# IO_combined.net
KiCad netlist of a schematic drawn in Altium Designer
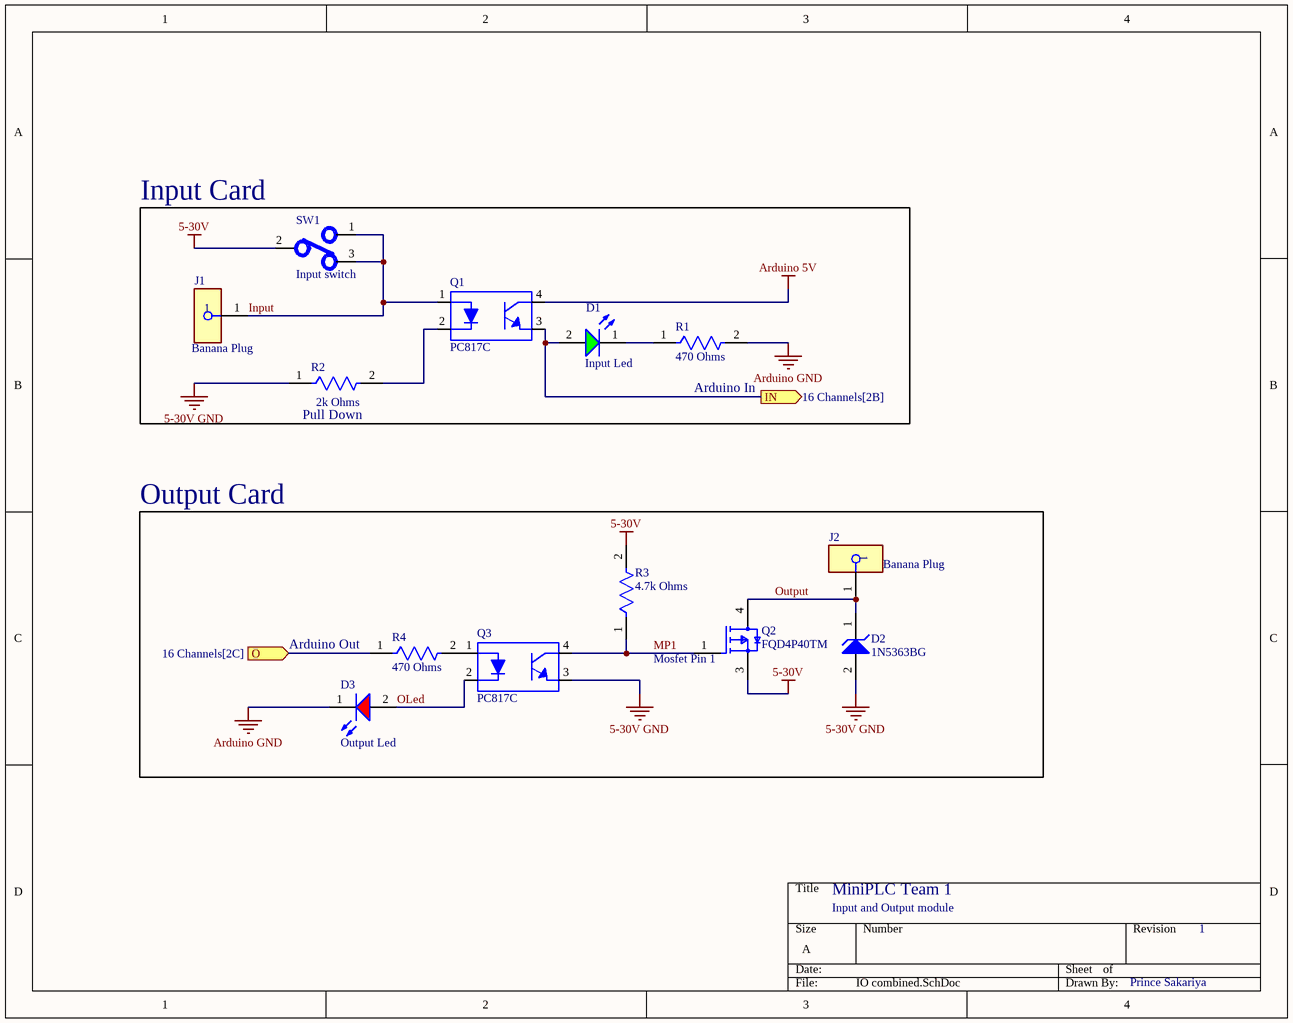
[diagram p0: IO combined.SchDoc]

(export (version "E")
  (design (tool "Eeschema 10.0.6"))
  (components
    (comp (ref "D1")
      (value "Input Led")
      (footprint "WL-TMRW_D5.8H8.6")
      (description "151054GS03000 WL-TMRW THT Mono-color Round Waterclear")
      (libsource (lib "Altium Content Vault") (part "LED_Green_2A-1K"))
    )
    (comp (ref "D2")
      (value "1N5363BG")
      (footprint "ONSC-SURMETIC40-2-017AA-01")
      (description "5 W Zener Voltage Regulator, 2-Pin Surmetic(TM) 40, Pb-Free, Bulk Box")
      (fields (field (name "MANUFACTURER") "On Semiconductor"))
      (libsource (lib "Altium Content Vault") (part "ONSC-K1A2-2"))
    )
    (comp (ref "D3")
      (value "Output Led")
      (footprint "WL-TMRW_D5.8H8.6")
      (description "151054RS03000 WL-TMRW THT Mono-color Round Waterclear")
      (libsource (lib "Altium Content Vault") (part "LED_Red_2A-1K"))
    )
    (comp (ref "J1")
      (value "Banana Plug")
      (footprint "FP-1581-5-MFG")
      (description "CONN BANANA JACK TURRET GREEN")
      (libsource (lib "Altium Content Vault") (part "c5c826e0c4b67fe3b42ef77f2d4decc"))
    )
    (comp (ref "J2")
      (value "Banana Plug")
      (footprint "FP-1581-5-MFG")
      (description "CONN BANANA JACK TURRET GREEN")
      (libsource (lib "") (part "c5c826e0c4b67fe3b42ef77f2d4decc_1"))
    )
    (comp (ref "Q1")
      (value "PC817C")
      (footprint "PC817-DIP")
      (description "Optoisolator Transistor Output 5000Vrms 1 Channel 4-DIP\r\n¦ Designed By @Alixahedi ¦")
      (fields (field (name "MF") "Taiwan Semiconductor"))
      (libsource (lib "SnapEDAsch") (part "PC817C"))
    )
    (comp (ref "Q2")
      (value "FQD4P40TM")
      (footprint "FP-369AS-MFG")
      (description "FQD4P40TM P-channel Power Mosfet, Qfet®, -400 V, -2.7 A, 3.1 Ω, Dpak")
      (libsource (lib "Altium Content Vault") (part "34928d9f04e0aab61442e227171e45b"))
    )
    (comp (ref "Q3")
      (value "PC817C")
      (footprint "PC817-DIP")
      (description "Optoisolator Transistor Output 5000Vrms 1 Channel 4-DIP\r\n¦ Designed By @Alixahedi ¦")
      (fields (field (name "MF") "Taiwan Semiconductor"))
      (libsource (lib "SnapEDAsch") (part "PC817C"))
    )
    (comp (ref "R1")
      (value "470 Ohms")
      (footprint "FP-HVR37-MFG")
      (fields (field (name "TOLERANCE") "1%"))
      (libsource (lib "Altium Content Vault") (part "1029c3af85768c4190bb7ad29bc67b5"))
    )
    (comp (ref "R2")
      (value "2k Ohms")
      (footprint "FP-HVR37-MFG")
      (fields (field (name "TOLERANCE") "1%"))
      (libsource (lib "Altium Content Vault") (part "1029c3af85768c4190bb7ad29bc67b5"))
    )
    (comp (ref "R3")
      (value "4.7k Ohms")
      (footprint "FP-HVR37-MFG")
      (fields (field (name "TOLERANCE") "1%"))
      (libsource (lib "Altium Content Vault") (part "1029c3af85768c4190bb7ad29bc67b5"))
    )
    (comp (ref "R4")
      (value "470 Ohms")
      (footprint "FP-HVR37-MFG")
      (fields (field (name "TOLERANCE") "1%"))
      (libsource (lib "Altium Content Vault") (part "1029c3af85768c4190bb7ad29bc67b5"))
    )
    (comp (ref "SW1")
      (value "Input switch")
      (footprint "Switch - duplicate")
      (description "WS-TOTV Toggle Switch")
      (fields
        (field (name "MANUFACTURER") "Wurth Electronics")
        (field (name "MANUFACTURER PART NUMBER") "472121020311")
      )
      (libsource (lib "NewSwitch") (part "472121020311"))
    )
  )
  (nets
    (net (code "1") (name "/IN") (class "Default")
      (node (ref "D1") (pin "2") (pinfunction "A_2") (pintype "passive"))
      (node (ref "Q1") (pin "3") (pinfunction "3_3") (pintype "passive"))
    )
    (net (code "2") (name "/Input") (class "Default")
      (node (ref "J1") (pin "1") (pinfunction "1_1") (pintype "passive"))
      (node (ref "Q1") (pin "1") (pinfunction "1_1") (pintype "passive"))
      (node (ref "SW1") (pin "1") (pinfunction "1_1") (pintype "passive"))
      (node (ref "SW1") (pin "3") (pinfunction "3_3") (pintype "passive"))
    )
    (net (code "3") (name "/MP1") (class "Default")
      (node (ref "Q2") (pin "1") (pinfunction "G_1") (pintype "passive"))
      (node (ref "Q3") (pin "4") (pinfunction "4_4") (pintype "passive"))
      (node (ref "R3") (pin "1") (pinfunction "1_1") (pintype "passive"))
    )
    (net (code "4") (name "/O") (class "Default")
      (node (ref "R4") (pin "1") (pinfunction "1_1") (pintype "passive"))
    )
    (net (code "5") (name "/OLed") (class "Default")
      (node (ref "D3") (pin "2") (pinfunction "A_2") (pintype "passive"))
      (node (ref "Q3") (pin "2") (pinfunction "2_2") (pintype "passive"))
    )
    (net (code "6") (name "/Output") (class "Default")
      (node (ref "D2") (pin "1") (pinfunction "K_1") (pintype "passive"))
      (node (ref "J2") (pin "1") (pinfunction "1_1") (pintype "passive"))
      (node (ref "Q2") (pin "4") (pinfunction "D_4") (pintype "passive"))
    )
    (net (code "7") (name "5-30V") (class "Default")
      (node (ref "Q2") (pin "3") (pinfunction "S_3") (pintype "passive"))
      (node (ref "R3") (pin "2") (pinfunction "2_2") (pintype "passive"))
      (node (ref "SW1") (pin "2") (pinfunction "2_2") (pintype "passive"))
    )
    (net (code "8") (name "5-30V GND") (class "Default")
      (node (ref "D2") (pin "2") (pinfunction "A_2") (pintype "passive"))
      (node (ref "Q3") (pin "3") (pinfunction "3_3") (pintype "passive"))
      (node (ref "R2") (pin "1") (pinfunction "1_1") (pintype "passive"))
    )
    (net (code "9") (name "Arduino 5V") (class "Default")
      (node (ref "Q1") (pin "4") (pinfunction "4_4") (pintype "passive"))
    )
    (net (code "10") (name "Arduino GND") (class "Default")
      (node (ref "D3") (pin "1") (pinfunction "K_1") (pintype "passive"))
      (node (ref "R1") (pin "2") (pinfunction "2_2") (pintype "passive"))
    )
    (net (code "11") (name "Net-(D1-K)") (class "Default")
      (node (ref "D1") (pin "1") (pinfunction "K_1") (pintype "passive"))
      (node (ref "R1") (pin "1") (pinfunction "1_1") (pintype "passive"))
    )
    (net (code "12") (name "Net-(Q1-Pad2)") (class "Default")
      (node (ref "Q1") (pin "2") (pinfunction "2_2") (pintype "passive"))
      (node (ref "R2") (pin "2") (pinfunction "2_2") (pintype "passive"))
    )
    (net (code "13") (name "Net-(Q3-Pad1)") (class "Default")
      (node (ref "Q3") (pin "1") (pinfunction "1_1") (pintype "passive"))
      (node (ref "R4") (pin "2") (pinfunction "2_2") (pintype "passive"))
    )
  )
)
